# tinyPipes_v2_6.net
KiCad netlist of a schematic drawn in EAGLE
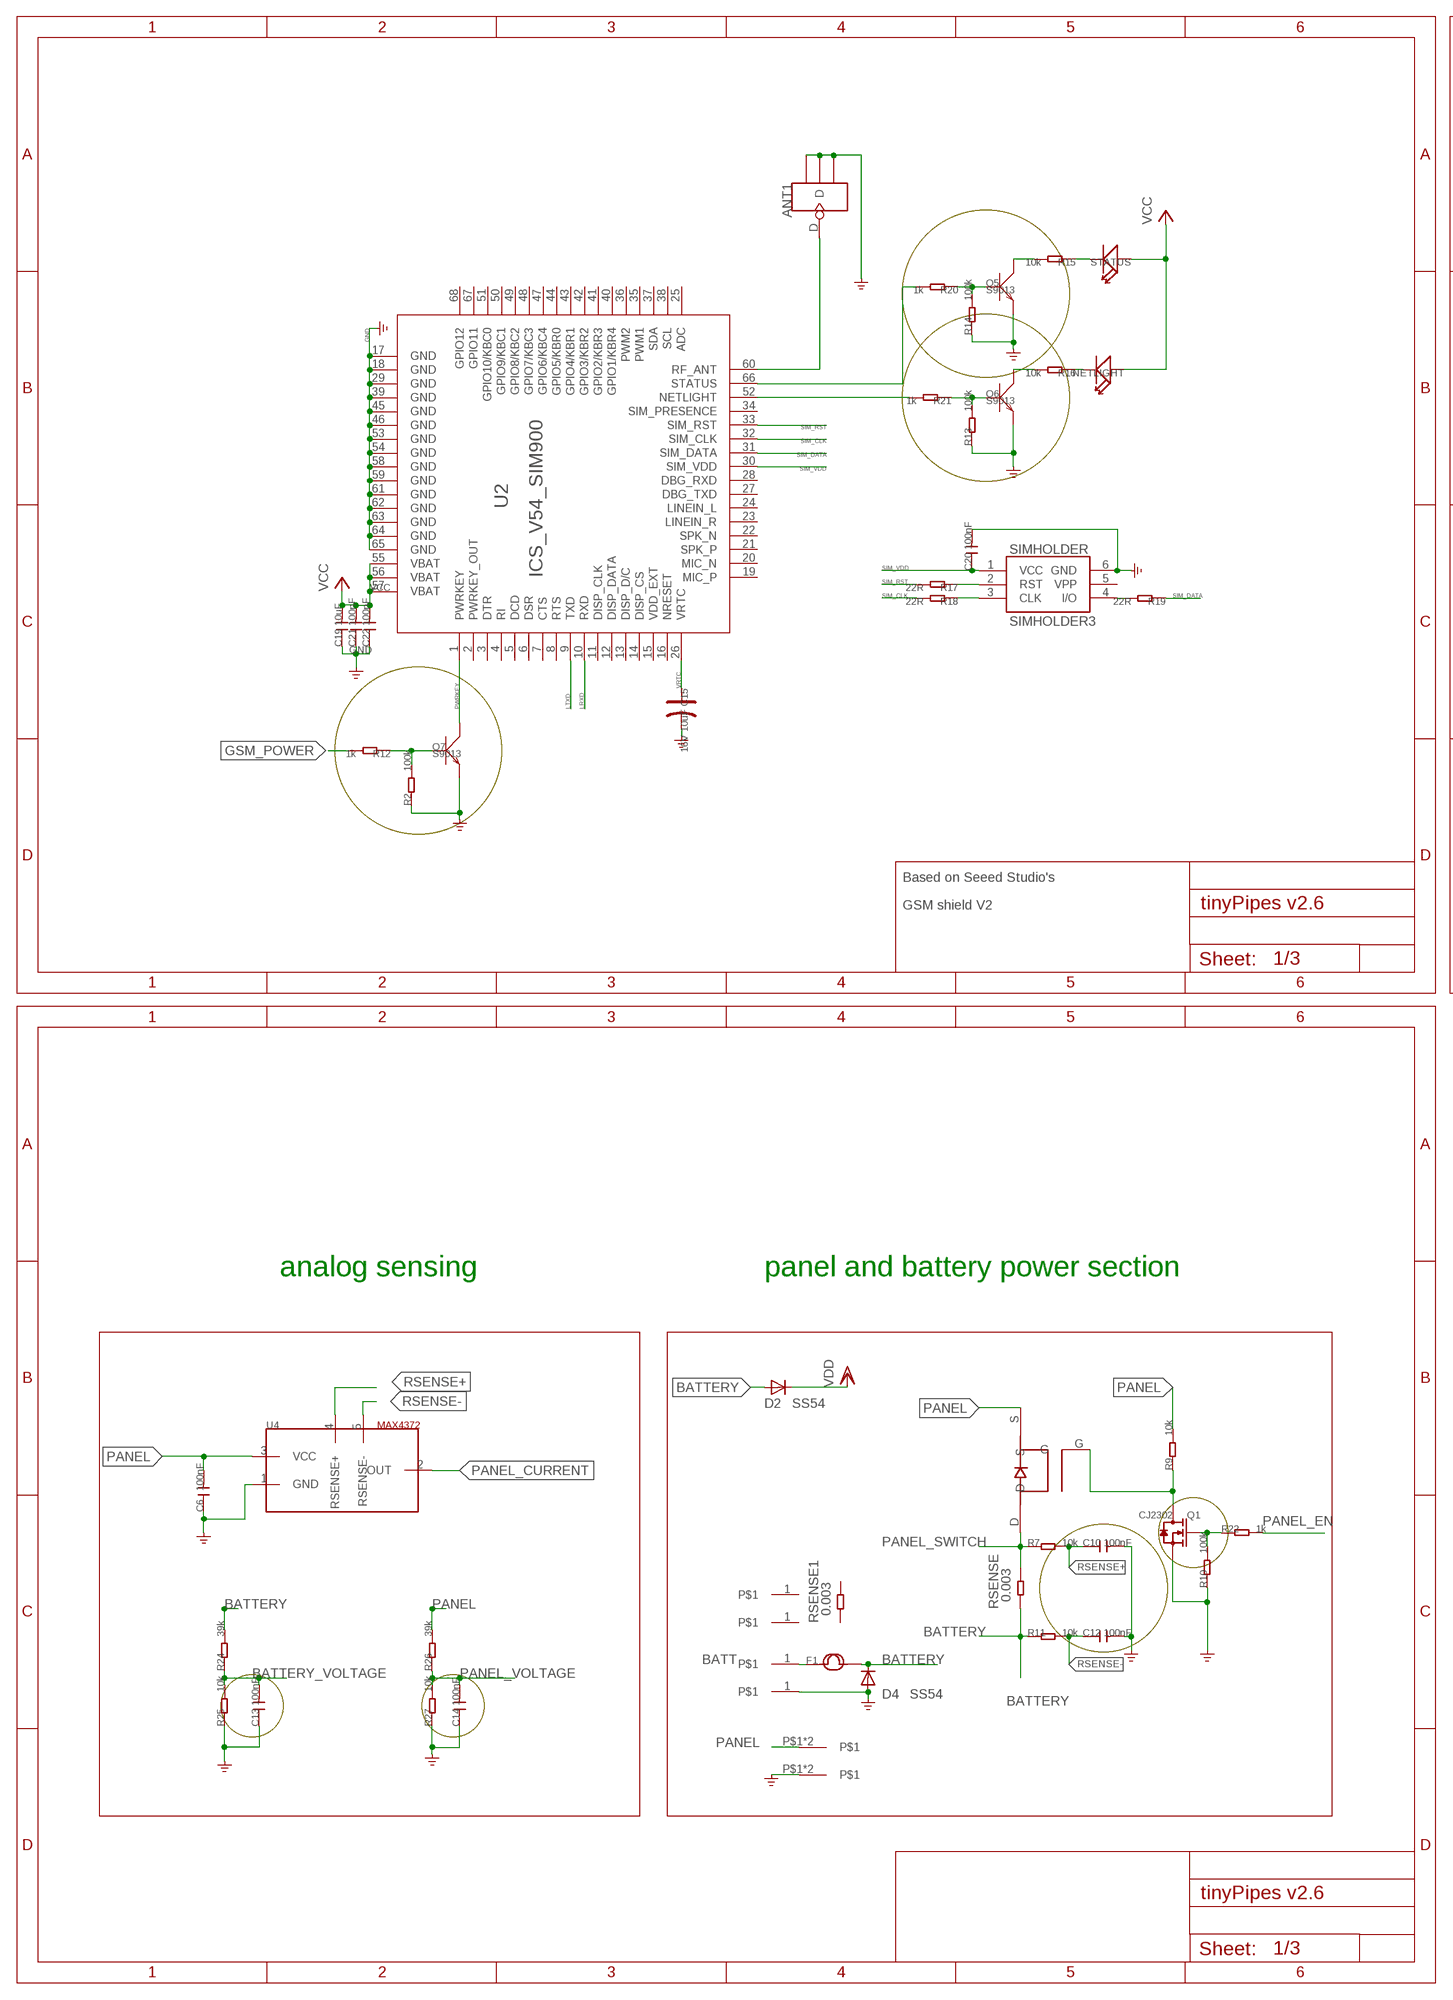
[diagram p0: schematic, sheet 1, part 1 of 2]
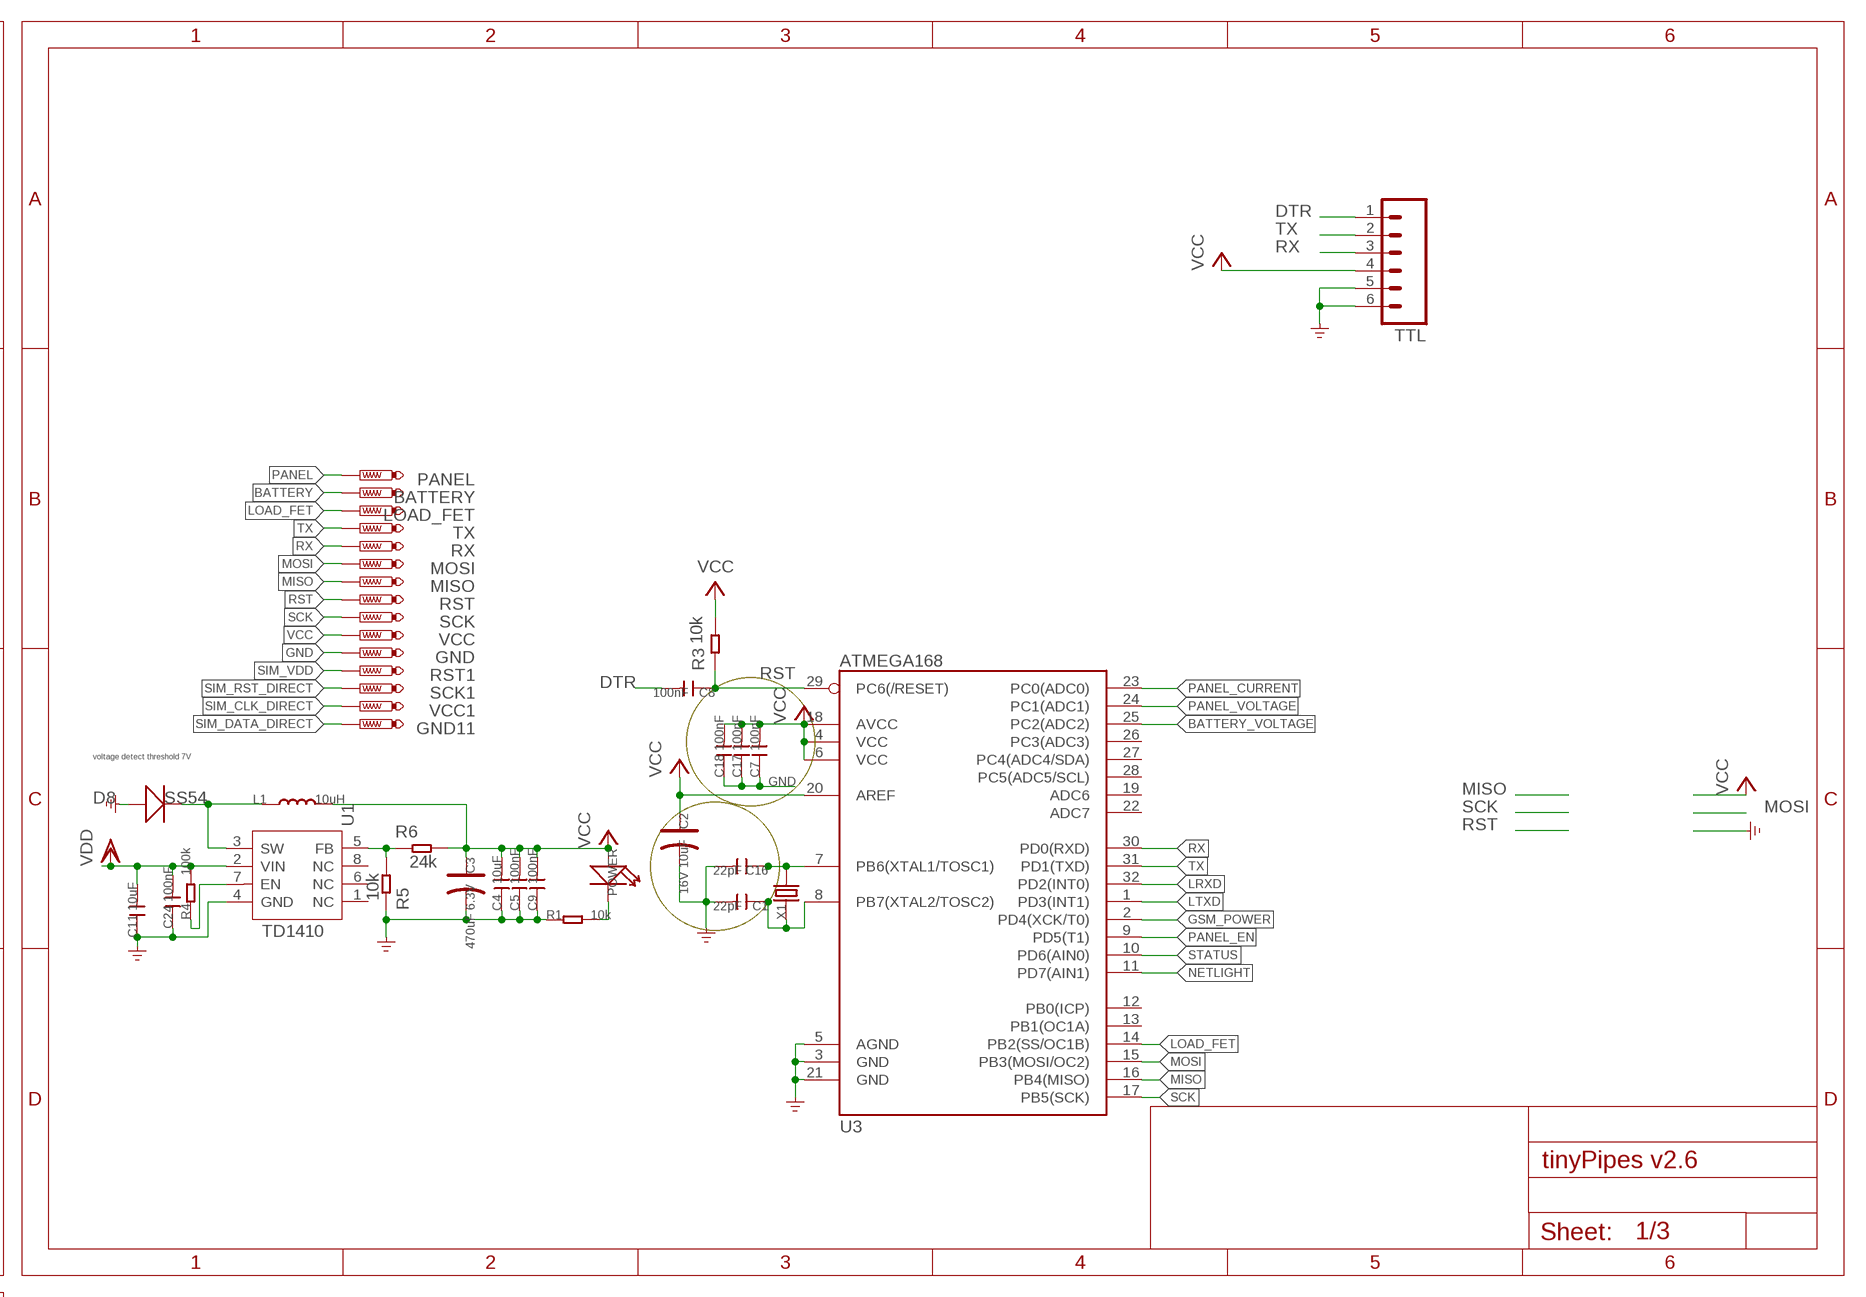
[diagram p1: schematic, sheet 1, part 2 of 2]

(export (version "E")
  (design (tool "Eeschema 10.0.6"))
  (components
    (comp (ref "ANT1")
      (value "ANTENNA-U-FL")
      (footprint "eagle-import:4P-U-FL")
      (libsource (lib "eagle-import") (part "ANTENNA-U-FL"))
    )
    (comp (ref "BATTERY")
      (value "PTR1B2,54")
      (footprint "eagle-import:B2,54")
      (libsource (lib "eagle-import") (part "PTR1B2,54"))
    )
    (comp (ref "BATTERY+")
      (value "TINYPIPES_BATTBATT")
      (footprint "eagle-import:TINYPIPES_BATT")
      (libsource (lib "eagle-import") (part "TINYPIPES_BATTBATT"))
    )
    (comp (ref "BATTERY+1")
      (value "TINYPIPES_BATTBATT")
      (footprint "eagle-import:TINYPIPES_BATT")
      (libsource (lib "eagle-import") (part "TINYPIPES_BATTBATT"))
    )
    (comp (ref "BATTERY-")
      (value "TINYPIPES_BATTBATT")
      (footprint "eagle-import:TINYPIPES_BATT")
      (libsource (lib "eagle-import") (part "TINYPIPES_BATTBATT"))
    )
    (comp (ref "BATTERY-1")
      (value "TINYPIPES_BATTBATT")
      (footprint "eagle-import:TINYPIPES_BATT")
      (libsource (lib "eagle-import") (part "TINYPIPES_BATTBATT"))
    )
    (comp (ref "C1")
      (value "22pF")
      (footprint "eagle-import:C0603")
      (libsource (lib "eagle-import") (part "C-0603"))
    )
    (comp (ref "C2")
      (value "16V 10uF")
      (footprint "eagle-import:AVX-A")
      (libsource (lib "eagle-import") (part "CAP-AVX-A"))
    )
    (comp (ref "C3")
      (value "470uF 6.3V")
      (footprint "eagle-import:AVX-D")
      (libsource (lib "eagle-import") (part "CAP-AVX-D"))
    )
    (comp (ref "C4")
      (value "10uF")
      (footprint "eagle-import:C0805")
      (libsource (lib "eagle-import") (part "C-0805"))
    )
    (comp (ref "C5")
      (value "100nF")
      (footprint "eagle-import:C0603")
      (libsource (lib "eagle-import") (part "C-0603"))
    )
    (comp (ref "C6")
      (value "100nF")
      (footprint "eagle-import:C0603")
      (libsource (lib "eagle-import") (part "C-0603"))
    )
    (comp (ref "C7")
      (value "100nF")
      (footprint "eagle-import:C0603")
      (libsource (lib "eagle-import") (part "C-0603"))
    )
    (comp (ref "C8")
      (value "100nF")
      (footprint "eagle-import:C0603")
      (libsource (lib "eagle-import") (part "C-0603"))
    )
    (comp (ref "C9")
      (value "100nF")
      (footprint "eagle-import:C0603")
      (libsource (lib "eagle-import") (part "C-0603"))
    )
    (comp (ref "C10")
      (value "100nF")
      (footprint "eagle-import:C0805")
      (libsource (lib "eagle-import") (part "C-0805"))
    )
    (comp (ref "C11")
      (value "10uF")
      (footprint "eagle-import:C0805")
      (libsource (lib "eagle-import") (part "C-0805"))
    )
    (comp (ref "C12")
      (value "100nF")
      (footprint "eagle-import:C0805")
      (libsource (lib "eagle-import") (part "C-0805"))
    )
    (comp (ref "C13")
      (value "100nF")
      (footprint "eagle-import:C0603")
      (libsource (lib "eagle-import") (part "C-0603"))
    )
    (comp (ref "C14")
      (value "100nF")
      (footprint "eagle-import:C0603")
      (libsource (lib "eagle-import") (part "C-0603"))
    )
    (comp (ref "C15")
      (value "16V 10uF")
      (footprint "eagle-import:AVX-A")
      (libsource (lib "eagle-import") (part "CAP-AVX-A"))
    )
    (comp (ref "C16")
      (value "22pF")
      (footprint "eagle-import:C0603")
      (libsource (lib "eagle-import") (part "C-0603"))
    )
    (comp (ref "C17")
      (value "100nF")
      (footprint "eagle-import:C0603")
      (libsource (lib "eagle-import") (part "C-0603"))
    )
    (comp (ref "C18")
      (value "100nF")
      (footprint "eagle-import:C0603")
      (libsource (lib "eagle-import") (part "C-0603"))
    )
    (comp (ref "C19")
      (value "10uF")
      (footprint "eagle-import:C0805")
      (libsource (lib "eagle-import") (part "C-0805"))
    )
    (comp (ref "C20")
      (value "100nF")
      (footprint "eagle-import:C0603")
      (libsource (lib "eagle-import") (part "C-0603"))
    )
    (comp (ref "C21")
      (value "100nF")
      (footprint "eagle-import:C0603")
      (libsource (lib "eagle-import") (part "C-0603"))
    )
    (comp (ref "C22")
      (value "100nF")
      (footprint "eagle-import:C0603")
      (libsource (lib "eagle-import") (part "C-0603"))
    )
    (comp (ref "C24")
      (value "100nF")
      (footprint "eagle-import:C0603")
      (libsource (lib "eagle-import") (part "C-0603"))
    )
    (comp (ref "D2")
      (value "SS54")
      (footprint "eagle-import:SMB")
      (libsource (lib "eagle-import") (part "DIODE-SMB"))
    )
    (comp (ref "D4")
      (value "SS54")
      (footprint "eagle-import:SMB")
      (libsource (lib "eagle-import") (part "DIODE-SMB"))
    )
    (comp (ref "D8")
      (value "SS54")
      (footprint "eagle-import:SMB")
      (libsource (lib "eagle-import") (part "D'MBRS240LT3'"))
    )
    (comp (ref "F1")
      (value "FUSE'16R700'")
      (footprint "eagle-import:0210")
      (libsource (lib "eagle-import") (part "FUSE'16R700'"))
    )
    (comp (ref "GND")
      (value "PTR1B2,54")
      (footprint "eagle-import:B2,54")
      (libsource (lib "eagle-import") (part "PTR1B2,54"))
    )
    (comp (ref "GND11")
      (value "PTR1B2,54")
      (footprint "eagle-import:B2,54")
      (libsource (lib "eagle-import") (part "PTR1B2,54"))
    )
    (comp (ref "L1")
      (value "10uH")
      (footprint "eagle-import:L0630")
      (libsource (lib "eagle-import") (part "L'0630'"))
    )
    (comp (ref "LOAD_FET")
      (value "PTR1B2,54")
      (footprint "eagle-import:B2,54")
      (libsource (lib "eagle-import") (part "PTR1B2,54"))
    )
    (comp (ref "MISO")
      (value "PTR1B2,54")
      (footprint "eagle-import:B2,54")
      (libsource (lib "eagle-import") (part "PTR1B2,54"))
    )
    (comp (ref "MOSI")
      (value "PTR1B2,54")
      (footprint "eagle-import:B2,54")
      (libsource (lib "eagle-import") (part "PTR1B2,54"))
    )
    (comp (ref "NETLIGHT")
      (value "LED'0603'")
      (footprint "eagle-import:LED-0603")
      (libsource (lib "eagle-import") (part "LED'0603'"))
    )
    (comp (ref "PANEL")
      (value "PTR1B2,54")
      (footprint "eagle-import:B2,54")
      (libsource (lib "eagle-import") (part "PTR1B2,54"))
    )
    (comp (ref "PANEL+")
      (value "TINYPIPES_BATTPANEL")
      (footprint "eagle-import:TINYPIPES_PANEL")
      (libsource (lib "eagle-import") (part "TINYPIPES_BATTPANEL"))
    )
    (comp (ref "PANEL-")
      (value "TINYPIPES_BATTPANEL")
      (footprint "eagle-import:TINYPIPES_PANEL")
      (libsource (lib "eagle-import") (part "TINYPIPES_BATTPANEL"))
    )
    (comp (ref "POWER")
      (value "LED'0603'")
      (footprint "eagle-import:LED-0603")
      (libsource (lib "eagle-import") (part "LED'0603'"))
    )
    (comp (ref "Q1")
      (value "CJ2302")
      (footprint "eagle-import:SOT23")
      (libsource (lib "eagle-import") (part "MOSFET-N'SOT23'"))
    )
    (comp (ref "Q5")
      (value "S9013")
      (footprint "eagle-import:SOT23")
      (libsource (lib "eagle-import") (part "TRANSISTOR-NPN-SOT23"))
    )
    (comp (ref "Q6")
      (value "S9013")
      (footprint "eagle-import:SOT23")
      (libsource (lib "eagle-import") (part "TRANSISTOR-NPN-SOT23"))
    )
    (comp (ref "Q7")
      (value "S9013")
      (footprint "eagle-import:SOT23")
      (libsource (lib "eagle-import") (part "TRANSISTOR-NPN-SOT23"))
    )
    (comp (ref "R1")
      (value "10k")
      (footprint "eagle-import:R0603")
      (libsource (lib "eagle-import") (part "R-0603"))
    )
    (comp (ref "R2")
      (value "100k")
      (footprint "eagle-import:R0603")
      (libsource (lib "eagle-import") (part "R-0603"))
    )
    (comp (ref "R3")
      (value "10k")
      (footprint "eagle-import:R0603")
      (libsource (lib "eagle-import") (part "R-0603"))
    )
    (comp (ref "R4")
      (value "100k")
      (footprint "eagle-import:R0603")
      (libsource (lib "eagle-import") (part "R-0603"))
    )
    (comp (ref "R5")
      (value "10k")
      (footprint "eagle-import:R0603")
      (libsource (lib "eagle-import") (part "R-0603"))
    )
    (comp (ref "R6")
      (value "24k")
      (footprint "eagle-import:R0603")
      (libsource (lib "eagle-import") (part "R-0603"))
    )
    (comp (ref "R7")
      (value "10k")
      (footprint "eagle-import:R0603")
      (libsource (lib "eagle-import") (part "R-0603"))
    )
    (comp (ref "R9")
      (value "10k")
      (footprint "eagle-import:R0603")
      (libsource (lib "eagle-import") (part "R-0603"))
    )
    (comp (ref "R10")
      (value "100k")
      (footprint "eagle-import:R0603")
      (libsource (lib "eagle-import") (part "R-0603"))
    )
    (comp (ref "R11")
      (value "10k")
      (footprint "eagle-import:R0603")
      (libsource (lib "eagle-import") (part "R-0603"))
    )
    (comp (ref "R12")
      (value "1k")
      (footprint "eagle-import:R0603")
      (libsource (lib "eagle-import") (part "R-0603"))
    )
    (comp (ref "R13")
      (value "100k")
      (footprint "eagle-import:R0603")
      (libsource (lib "eagle-import") (part "R-0603"))
    )
    (comp (ref "R14")
      (value "100k")
      (footprint "eagle-import:R0603")
      (libsource (lib "eagle-import") (part "R-0603"))
    )
    (comp (ref "R15")
      (value "10k")
      (footprint "eagle-import:R0603")
      (libsource (lib "eagle-import") (part "R-0603"))
    )
    (comp (ref "R16")
      (value "10k")
      (footprint "eagle-import:R0603")
      (libsource (lib "eagle-import") (part "R-0603"))
    )
    (comp (ref "R17")
      (value "22R")
      (footprint "eagle-import:R0603")
      (libsource (lib "eagle-import") (part "R-0603"))
    )
    (comp (ref "R18")
      (value "22R")
      (footprint "eagle-import:R0603")
      (libsource (lib "eagle-import") (part "R-0603"))
    )
    (comp (ref "R19")
      (value "22R")
      (footprint "eagle-import:R0603")
      (libsource (lib "eagle-import") (part "R-0603"))
    )
    (comp (ref "R20")
      (value "1k")
      (footprint "eagle-import:R0603")
      (libsource (lib "eagle-import") (part "R-0603"))
    )
    (comp (ref "R21")
      (value "1k")
      (footprint "eagle-import:R0603")
      (libsource (lib "eagle-import") (part "R-0603"))
    )
    (comp (ref "R22")
      (value "1k")
      (footprint "eagle-import:R0603")
      (libsource (lib "eagle-import") (part "R-0603"))
    )
    (comp (ref "R24")
      (value "39k")
      (footprint "eagle-import:R0603")
      (libsource (lib "eagle-import") (part "R-0603"))
    )
    (comp (ref "R25")
      (value "10k")
      (footprint "eagle-import:R0603")
      (libsource (lib "eagle-import") (part "R-0603"))
    )
    (comp (ref "R26")
      (value "39k")
      (footprint "eagle-import:R0603")
      (libsource (lib "eagle-import") (part "R-0603"))
    )
    (comp (ref "R27")
      (value "10k")
      (footprint "eagle-import:R0603")
      (libsource (lib "eagle-import") (part "R-0603"))
    )
    (comp (ref "RSENSE")
      (value "0.003")
      (footprint "eagle-import:R2512")
      (libsource (lib "eagle-import") (part "R-2512"))
    )
    (comp (ref "RSENSE1")
      (value "0.003")
      (footprint "eagle-import:R2512")
      (libsource (lib "eagle-import") (part "R-2512"))
    )
    (comp (ref "RST")
      (value "PTR1B2,54")
      (footprint "eagle-import:B2,54")
      (libsource (lib "eagle-import") (part "PTR1B2,54"))
    )
    (comp (ref "RST1")
      (value "PTR1B2,54")
      (footprint "eagle-import:B2,54")
      (libsource (lib "eagle-import") (part "PTR1B2,54"))
    )
    (comp (ref "RX")
      (value "PTR1B2,54")
      (footprint "eagle-import:B2,54")
      (libsource (lib "eagle-import") (part "PTR1B2,54"))
    )
    (comp (ref "SCK")
      (value "PTR1B2,54")
      (footprint "eagle-import:B2,54")
      (libsource (lib "eagle-import") (part "PTR1B2,54"))
    )
    (comp (ref "SCK1")
      (value "PTR1B2,54")
      (footprint "eagle-import:B2,54")
      (libsource (lib "eagle-import") (part "PTR1B2,54"))
    )
    (comp (ref "SIMHOLDER")
      (value "SIMHOLDER3")
      (footprint "eagle-import:SIMHOLDER3")
      (libsource (lib "eagle-import") (part "SIMHOLDER3"))
    )
    (comp (ref "STATUS")
      (value "LED'0603'")
      (footprint "eagle-import:LED-0603")
      (libsource (lib "eagle-import") (part "LED'0603'"))
    )
    (comp (ref "TTL")
      (value "M06LOCK")
      (footprint "eagle-import:1X06_LOCK")
      (libsource (lib "eagle-import") (part "M06LOCK"))
    )
    (comp (ref "TX")
      (value "PTR1B2,54")
      (footprint "eagle-import:B2,54")
      (libsource (lib "eagle-import") (part "PTR1B2,54"))
    )
    (comp (ref "U1")
      (value "TD1410")
      (footprint "eagle-import:SOP8")
      (libsource (lib "eagle-import") (part "TD1410"))
    )
    (comp (ref "U2")
      (value "ICS_V54_SIM900")
      (footprint "eagle-import:ICS_V54_SIM900")
      (libsource (lib "eagle-import") (part "ICS_V54_SIM900"))
    )
    (comp (ref "U3")
      (value "ATMEGA168")
      (footprint "eagle-import:TQFP32-08")
      (libsource (lib "eagle-import") (part "ATMEGA168"))
    )
    (comp (ref "U4")
      (value "MAX4372")
      (footprint "eagle-import:SOT23-5")
      (libsource (lib "eagle-import") (part "MAX4372"))
    )
    (comp (ref "U5")
      (value "SI4435POWER")
      (footprint "eagle-import:SO8_FET")
      (libsource (lib "eagle-import") (part "SI4435POWER"))
    )
    (comp (ref "VCC")
      (value "PTR1B2,54")
      (footprint "eagle-import:B2,54")
      (libsource (lib "eagle-import") (part "PTR1B2,54"))
    )
    (comp (ref "VCC1")
      (value "PTR1B2,54")
      (footprint "eagle-import:B2,54")
      (libsource (lib "eagle-import") (part "PTR1B2,54"))
    )
    (comp (ref "X1")
      (value "CRYSTAL'5032'")
      (footprint "eagle-import:2P-SMD-5X3.2")
      (libsource (lib "eagle-import") (part "CRYSTAL'5032'"))
    )
  )
  (nets
    (net (code "1") (name "BATT") (class "Default")
      (node (ref "BATTERY+") (pin "1") (pinfunction "P$1_1") (pintype "bidirectional"))
      (node (ref "F1") (pin "1") (pinfunction "1_1") (pintype "bidirectional"))
    )
    (net (code "2") (name "BATTERY") (class "Default")
      (node (ref "BATTERY") (pin "TP") (pinfunction "TP_TP") (pintype "input"))
      (node (ref "D2") (pin "A") (pinfunction "A_A") (pintype "passive"))
      (node (ref "D4") (pin "C") (pinfunction "C_C") (pintype "passive"))
      (node (ref "F1") (pin "2") (pinfunction "2_2") (pintype "bidirectional"))
      (node (ref "R11") (pin "1") (pinfunction "1_1") (pintype "passive"))
      (node (ref "R24") (pin "2") (pinfunction "2_2") (pintype "passive"))
      (node (ref "RSENSE") (pin "1") (pinfunction "1_1") (pintype "passive"))
    )
    (net (code "3") (name "BATTERY_VOLTAGE") (class "Default")
      (node (ref "C13") (pin "2") (pinfunction "2_2") (pintype "passive"))
      (node (ref "R24") (pin "1") (pinfunction "1_1") (pintype "passive"))
      (node (ref "R25") (pin "2") (pinfunction "2_2") (pintype "passive"))
      (node (ref "U3") (pin "25") (pinfunction "PC2(ADC2)_25") (pintype "bidirectional"))
    )
    (net (code "4") (name "DTR") (class "Default")
      (node (ref "C8") (pin "2") (pinfunction "2_2") (pintype "passive"))
      (node (ref "TTL") (pin "1") (pinfunction "1_1") (pintype "passive"))
    )
    (net (code "5") (name "GND") (class "Default")
      (node (ref "ANT1") (pin "GND1") (pinfunction "GND1_GND1") (pintype "bidirectional"))
      (node (ref "ANT1") (pin "GND2") (pinfunction "GND2_GND2") (pintype "bidirectional"))
      (node (ref "ANT1") (pin "GND3") (pinfunction "GND3_GND3") (pintype "bidirectional"))
      (node (ref "BATTERY-") (pin "1") (pinfunction "P$1_1") (pintype "bidirectional"))
      (node (ref "C1") (pin "2") (pinfunction "2_2") (pintype "passive"))
      (node (ref "C10") (pin "2") (pinfunction "2_2") (pintype "passive"))
      (node (ref "C11") (pin "1") (pinfunction "1_1") (pintype "passive"))
      (node (ref "C12") (pin "2") (pinfunction "2_2") (pintype "passive"))
      (node (ref "C13") (pin "1") (pinfunction "1_1") (pintype "passive"))
      (node (ref "C14") (pin "1") (pinfunction "1_1") (pintype "passive"))
      (node (ref "C15") (pin "-") (pinfunction "-_-") (pintype "passive"))
      (node (ref "C16") (pin "2") (pinfunction "2_2") (pintype "passive"))
      (node (ref "C17") (pin "1") (pinfunction "1_1") (pintype "passive"))
      (node (ref "C18") (pin "1") (pinfunction "1_1") (pintype "passive"))
      (node (ref "C19") (pin "1") (pinfunction "1_1") (pintype "passive"))
      (node (ref "C2") (pin "-") (pinfunction "-_-") (pintype "passive"))
      (node (ref "C20") (pin "2") (pinfunction "2_2") (pintype "passive"))
      (node (ref "C21") (pin "1") (pinfunction "1_1") (pintype "passive"))
      (node (ref "C22") (pin "1") (pinfunction "1_1") (pintype "passive"))
      (node (ref "C24") (pin "1") (pinfunction "1_1") (pintype "passive"))
      (node (ref "C3") (pin "-") (pinfunction "-_-") (pintype "passive"))
      (node (ref "C4") (pin "1") (pinfunction "1_1") (pintype "passive"))
      (node (ref "C5") (pin "1") (pinfunction "1_1") (pintype "passive"))
      (node (ref "C6") (pin "1") (pinfunction "1_1") (pintype "passive"))
      (node (ref "C7") (pin "1") (pinfunction "1_1") (pintype "passive"))
      (node (ref "C9") (pin "1") (pinfunction "1_1") (pintype "passive"))
      (node (ref "D4") (pin "A") (pinfunction "A_A") (pintype "passive"))
      (node (ref "D8") (pin "+") (pinfunction "+_+") (pintype "passive"))
      (node (ref "GND") (pin "TP") (pinfunction "TP_TP") (pintype "input"))
      (node (ref "PANEL-") (pin "P$1") (pinfunction "P$1_P$1") (pintype "bidirectional"))
      (node (ref "PANEL-") (pin "P$2") (pinfunction "P$1_P$2") (pintype "bidirectional"))
      (node (ref "Q1") (pin "2") (pinfunction "S_2") (pintype "passive"))
      (node (ref "Q5") (pin "2") (pinfunction "E_2") (pintype "passive"))
      (node (ref "Q6") (pin "2") (pinfunction "E_2") (pintype "passive"))
      (node (ref "Q7") (pin "2") (pinfunction "E_2") (pintype "passive"))
      (node (ref "R1") (pin "1") (pinfunction "1_1") (pintype "passive"))
      (node (ref "R10") (pin "1") (pinfunction "1_1") (pintype "passive"))
      (node (ref "R13") (pin "1") (pinfunction "1_1") (pintype "passive"))
      (node (ref "R14") (pin "1") (pinfunction "1_1") (pintype "passive"))
      (node (ref "R2") (pin "1") (pinfunction "1_1") (pintype "passive"))
      (node (ref "R25") (pin "1") (pinfunction "1_1") (pintype "passive"))
      (node (ref "R27") (pin "1") (pinfunction "1_1") (pintype "passive"))
      (node (ref "R5") (pin "2") (pinfunction "2_2") (pintype "passive"))
      (node (ref "SIMHOLDER") (pin "6") (pinfunction "GND_6") (pintype "bidirectional"))
      (node (ref "TTL") (pin "5") (pinfunction "5_5") (pintype "passive"))
      (node (ref "TTL") (pin "6") (pinfunction "6_6") (pintype "passive"))
      (node (ref "U1") (pin "4") (pinfunction "GND_4") (pintype "power_in"))
      (node (ref "U2") (pin "17") (pinfunction "GND_17") (pintype "power_in"))
      (node (ref "U2") (pin "18") (pinfunction "GND_18") (pintype "power_in"))
      (node (ref "U2") (pin "29") (pinfunction "GND_29") (pintype "power_in"))
      (node (ref "U2") (pin "39") (pinfunction "GND_39") (pintype "power_in"))
      (node (ref "U2") (pin "45") (pinfunction "GND_45") (pintype "power_in"))
      (node (ref "U2") (pin "46") (pinfunction "GND_46") (pintype "power_in"))
      (node (ref "U2") (pin "53") (pinfunction "GND_53") (pintype "power_in"))
      (node (ref "U2") (pin "54") (pinfunction "GND_54") (pintype "power_in"))
      (node (ref "U2") (pin "58") (pinfunction "GND_58") (pintype "power_in"))
      (node (ref "U2") (pin "59") (pinfunction "GND_59") (pintype "power_in"))
      (node (ref "U2") (pin "61") (pinfunction "GND_61") (pintype "power_in"))
      (node (ref "U2") (pin "62") (pinfunction "GND_62") (pintype "power_in"))
      (node (ref "U2") (pin "63") (pinfunction "GND_63") (pintype "power_in"))
      (node (ref "U2") (pin "64") (pinfunction "GND_64") (pintype "power_in"))
      (node (ref "U2") (pin "65") (pinfunction "GND_65") (pintype "power_in"))
      (node (ref "U3") (pin "21") (pinfunction "GND_21") (pintype "bidirectional"))
      (node (ref "U3") (pin "3") (pinfunction "GND_3") (pintype "bidirectional"))
      (node (ref "U3") (pin "5") (pinfunction "AGND_5") (pintype "bidirectional"))
      (node (ref "U4") (pin "1") (pinfunction "GND_1") (pintype "bidirectional"))
    )
    (net (code "6") (name "GSM_POWER") (class "Default")
      (node (ref "R12") (pin "2") (pinfunction "2_2") (pintype "passive"))
      (node (ref "U3") (pin "2") (pinfunction "PD4(XCK/T0)_2") (pintype "bidirectional"))
    )
    (net (code "7") (name "LOAD_FET") (class "Default")
      (node (ref "LOAD_FET") (pin "TP") (pinfunction "TP_TP") (pintype "input"))
      (node (ref "U3") (pin "14") (pinfunction "PB2(SS/OC1B)_14") (pintype "bidirectional"))
    )
    (net (code "8") (name "LRXD") (class "Default")
      (node (ref "U2") (pin "10") (pinfunction "RXD_10") (pintype "input"))
      (node (ref "U3") (pin "32") (pinfunction "PD2(INT0)_32") (pintype "bidirectional"))
    )
    (net (code "9") (name "LTXD") (class "Default")
      (node (ref "U2") (pin "9") (pinfunction "TXD_9") (pintype "output"))
      (node (ref "U3") (pin "1") (pinfunction "PD3(INT1)_1") (pintype "bidirectional"))
    )
    (net (code "10") (name "MISO") (class "Default")
      (node (ref "MISO") (pin "TP") (pinfunction "TP_TP") (pintype "input"))
      (node (ref "U3") (pin "16") (pinfunction "PB4(MISO)_16") (pintype "bidirectional"))
    )
    (net (code "11") (name "MOSI") (class "Default")
      (node (ref "MOSI") (pin "TP") (pinfunction "TP_TP") (pintype "input"))
      (node (ref "U3") (pin "15") (pinfunction "PB3(MOSI/OC2)_15") (pintype "bidirectional"))
    )
    (net (code "12") (name "NETLIGHT") (class "Default")
      (node (ref "R21") (pin "2") (pinfunction "2_2") (pintype "passive"))
      (node (ref "U2") (pin "52") (pinfunction "NETLIGHT_52") (pintype "output"))
      (node (ref "U3") (pin "11") (pinfunction "PD7(AIN1)_11") (pintype "bidirectional"))
    )
    (net (code "13") (name "Net-(NETLIGHT-Pad-)") (class "Default")
      (node (ref "NETLIGHT") (pin "-") (pinfunction "-_-") (pintype "passive"))
      (node (ref "R16") (pin "1") (pinfunction "1_1") (pintype "passive"))
    )
    (net (code "14") (name "Net-(POWER-Pad-)") (class "Default")
      (node (ref "POWER") (pin "-") (pinfunction "-_-") (pintype "passive"))
      (node (ref "R1") (pin "2") (pinfunction "2_2") (pintype "passive"))
    )
    (net (code "15") (name "Net-(Q1-D)") (class "Default")
      (node (ref "Q1") (pin "3") (pinfunction "D_3") (pintype "passive"))
      (node (ref "R9") (pin "1") (pinfunction "1_1") (pintype "passive"))
      (node (ref "U5") (pin "G") (pinfunction "G_G") (pintype "bidirectional"))
    )
    (net (code "16") (name "Net-(Q1-G)") (class "Default")
      (node (ref "Q1") (pin "1") (pinfunction "G_1") (pintype "passive"))
      (node (ref "R10") (pin "2") (pinfunction "2_2") (pintype "passive"))
      (node (ref "R22") (pin "1") (pinfunction "1_1") (pintype "passive"))
    )
    (net (code "17") (name "Net-(Q5-B)") (class "Default")
      (node (ref "Q5") (pin "1") (pinfunction "B_1") (pintype "passive"))
      (node (ref "R14") (pin "2") (pinfunction "2_2") (pintype "passive"))
      (node (ref "R20") (pin "1") (pinfunction "1_1") (pintype "passive"))
    )
    (net (code "18") (name "Net-(Q5-C)") (class "Default")
      (node (ref "Q5") (pin "3") (pinfunction "C_3") (pintype "passive"))
      (node (ref "R15") (pin "2") (pinfunction "2_2") (pintype "passive"))
    )
    (net (code "19") (name "Net-(Q6-B)") (class "Default")
      (node (ref "Q6") (pin "1") (pinfunction "B_1") (pintype "passive"))
      (node (ref "R13") (pin "2") (pinfunction "2_2") (pintype "passive"))
      (node (ref "R21") (pin "1") (pinfunction "1_1") (pintype "passive"))
    )
    (net (code "20") (name "Net-(Q6-C)") (class "Default")
      (node (ref "Q6") (pin "3") (pinfunction "C_3") (pintype "passive"))
      (node (ref "R16") (pin "2") (pinfunction "2_2") (pintype "passive"))
    )
    (net (code "21") (name "Net-(Q7-B)") (class "Default")
      (node (ref "Q7") (pin "1") (pinfunction "B_1") (pintype "passive"))
      (node (ref "R12") (pin "1") (pinfunction "1_1") (pintype "passive"))
      (node (ref "R2") (pin "2") (pinfunction "2_2") (pintype "passive"))
    )
    (net (code "22") (name "Net-(R15-Pad1)") (class "Default")
      (node (ref "R15") (pin "1") (pinfunction "1_1") (pintype "passive"))
      (node (ref "STATUS") (pin "-") (pinfunction "-_-") (pintype "passive"))
    )
    (net (code "23") (name "Net-(U1-EN)") (class "Default")
      (node (ref "R4") (pin "1") (pinfunction "1_1") (pintype "passive"))
      (node (ref "U1") (pin "7") (pinfunction "EN_7") (pintype "input"))
    )
    (net (code "24") (name "Net-(U1-FB)") (class "Default")
      (node (ref "R5") (pin "1") (pinfunction "1_1") (pintype "passive"))
      (node (ref "R6") (pin "1") (pinfunction "1_1") (pintype "passive"))
      (node (ref "U1") (pin "5") (pinfunction "FB_5") (pintype "input"))
    )
    (net (code "25") (name "Net-(U1-SW)") (class "Default")
      (node (ref "D8") (pin "-") (pinfunction "-_-") (pintype "passive"))
      (node (ref "L1") (pin "1") (pinfunction "1_1") (pintype "passive"))
      (node (ref "U1") (pin "3") (pinfunction "SW_3") (pintype "output"))
    )
    (net (code "26") (name "Net-(U2-RF_ANT)") (class "Default")
      (node (ref "ANT1") (pin "D") (pinfunction "D_D") (pintype "bidirectional"))
      (node (ref "U2") (pin "60") (pinfunction "RF_ANT_60") (pintype "bidirectional"))
    )
    (net (code "27") (name "Net-(U3-PB6(XTAL1{slash}TOSC1))") (class "Default")
      (node (ref "C16") (pin "1") (pinfunction "1_1") (pintype "passive"))
      (node (ref "U3") (pin "7") (pinfunction "PB6(XTAL1/TOSC1)_7") (pintype "bidirectional"))
      (node (ref "X1") (pin "2") (pinfunction "2_2") (pintype "passive"))
    )
    (net (code "28") (name "Net-(U3-PB7(XTAL2{slash}TOSC2))") (class "Default")
      (node (ref "C1") (pin "1") (pinfunction "1_1") (pintype "passive"))
      (node (ref "U3") (pin "8") (pinfunction "PB7(XTAL2/TOSC2)_8") (pintype "bidirectional"))
      (node (ref "X1") (pin "1") (pinfunction "1_1") (pintype "passive"))
    )
    (net (code "29") (name "PANEL") (class "Default")
      (node (ref "C6") (pin "2") (pinfunction "2_2") (pintype "passive"))
      (node (ref "PANEL") (pin "TP") (pinfunction "TP_TP") (pintype "input"))
      (node (ref "PANEL+") (pin "P$1") (pinfunction "P$1_P$1") (pintype "bidirectional"))
      (node (ref "PANEL+") (pin "P$2") (pinfunction "P$1_P$2") (pintype "bidirectional"))
      (node (ref "R26") (pin "2") (pinfunction "2_2") (pintype "passive"))
      (node (ref "R9") (pin "2") (pinfunction "2_2") (pintype "passive"))
      (node (ref "U4") (pin "3") (pinfunction "VCC_3") (pintype "bidirectional"))
      (node (ref "U5") (pin "S") (pinfunction "S_S") (pintype "bidirectional"))
    )
    (net (code "30") (name "PANEL_CURRENT") (class "Default")
      (node (ref "U3") (pin "23") (pinfunction "PC0(ADC0)_23") (pintype "bidirectional"))
      (node (ref "U4") (pin "2") (pinfunction "OUT_2") (pintype "bidirectional"))
    )
    (net (code "31") (name "PANEL_EN") (class "Default")
      (node (ref "R22") (pin "2") (pinfunction "2_2") (pintype "passive"))
      (node (ref "U3") (pin "9") (pinfunction "PD5(T1)_9") (pintype "bidirectional"))
    )
    (net (code "32") (name "PANEL_SWITCH") (class "Default")
      (node (ref "R7") (pin "1") (pinfunction "1_1") (pintype "passive"))
      (node (ref "RSENSE") (pin "2") (pinfunction "2_2") (pintype "passive"))
      (node (ref "U5") (pin "D") (pinfunction "D_D") (pintype "bidirectional"))
    )
    (net (code "33") (name "PANEL_VOLTAGE") (class "Default")
      (node (ref "C14") (pin "2") (pinfunction "2_2") (pintype "passive"))
      (node (ref "R26") (pin "1") (pinfunction "1_1") (pintype "passive"))
      (node (ref "R27") (pin "2") (pinfunction "2_2") (pintype "passive"))
      (node (ref "U3") (pin "24") (pinfunction "PC1(ADC1)_24") (pintype "bidirectional"))
    )
    (net (code "34") (name "PWRKEY") (class "Default")
      (node (ref "Q7") (pin "3") (pinfunction "C_3") (pintype "passive"))
      (node (ref "U2") (pin "1") (pinfunction "PWRKEY_1") (pintype "input"))
    )
    (net (code "35") (name "RSENSE+") (class "Default")
      (node (ref "C10") (pin "1") (pinfunction "1_1") (pintype "passive"))
      (node (ref "R7") (pin "2") (pinfunction "2_2") (pintype "passive"))
      (node (ref "U4") (pin "4") (pinfunction "RSENSE+_4") (pintype "bidirectional"))
    )
    (net (code "36") (name "RSENSE-") (class "Default")
      (node (ref "C12") (pin "1") (pinfunction "1_1") (pintype "passive"))
      (node (ref "R11") (pin "2") (pinfunction "2_2") (pintype "passive"))
      (node (ref "U4") (pin "5") (pinfunction "RSENSE-_5") (pintype "bidirectional"))
    )
    (net (code "37") (name "RST") (class "Default")
      (node (ref "C8") (pin "1") (pinfunction "1_1") (pintype "passive"))
      (node (ref "R3") (pin "1") (pinfunction "1_1") (pintype "passive"))
      (node (ref "RST") (pin "TP") (pinfunction "TP_TP") (pintype "input"))
      (node (ref "U3") (pin "29") (pinfunction "PC6(/RESET)_29") (pintype "bidirectional"))
    )
    (net (code "38") (name "RX") (class "Default")
      (node (ref "RX") (pin "TP") (pinfunction "TP_TP") (pintype "input"))
      (node (ref "TTL") (pin "3") (pinfunction "3_3") (pintype "passive"))
      (node (ref "U3") (pin "30") (pinfunction "PD0(RXD)_30") (pintype "bidirectional"))
    )
    (net (code "39") (name "SCK") (class "Default")
      (node (ref "SCK") (pin "TP") (pinfunction "TP_TP") (pintype "input"))
      (node (ref "U3") (pin "17") (pinfunction "PB5(SCK)_17") (pintype "bidirectional"))
    )
    (net (code "40") (name "SIM_CLK") (class "Default")
      (node (ref "R18") (pin "2") (pinfunction "2_2") (pintype "passive"))
      (node (ref "U2") (pin "32") (pinfunction "SIM_CLK_32") (pintype "output"))
    )
    (net (code "41") (name "SIM_CLK_DIRECT") (class "Default")
      (node (ref "R18") (pin "1") (pinfunction "1_1") (pintype "passive"))
      (node (ref "SIMHOLDER") (pin "3") (pinfunction "CLK_3") (pintype "bidirectional"))
      (node (ref "VCC1") (pin "TP") (pinfunction "TP_TP") (pintype "input"))
    )
    (net (code "42") (name "SIM_DATA") (class "Default")
      (node (ref "R19") (pin "1") (pinfunction "1_1") (pintype "passive"))
      (node (ref "U2") (pin "31") (pinfunction "SIM_DATA_31") (pintype "bidirectional"))
    )
    (net (code "43") (name "SIM_DATA_DIRECT") (class "Default")
      (node (ref "GND11") (pin "TP") (pinfunction "TP_TP") (pintype "input"))
      (node (ref "R19") (pin "2") (pinfunction "2_2") (pintype "passive"))
      (node (ref "SIMHOLDER") (pin "4") (pinfunction "I/O_4") (pintype "bidirectional"))
    )
    (net (code "44") (name "SIM_RST") (class "Default")
      (node (ref "R17") (pin "2") (pinfunction "2_2") (pintype "passive"))
      (node (ref "U2") (pin "33") (pinfunction "SIM_RST_33") (pintype "output"))
    )
    (net (code "45") (name "SIM_RST_DIRECT") (class "Default")
      (node (ref "R17") (pin "1") (pinfunction "1_1") (pintype "passive"))
      (node (ref "SCK1") (pin "TP") (pinfunction "TP_TP") (pintype "input"))
      (node (ref "SIMHOLDER") (pin "2") (pinfunction "RST_2") (pintype "bidirectional"))
    )
    (net (code "46") (name "SIM_VDD") (class "Default")
      (node (ref "C20") (pin "1") (pinfunction "1_1") (pintype "passive"))
      (node (ref "RST1") (pin "TP") (pinfunction "TP_TP") (pintype "input"))
      (node (ref "SIMHOLDER") (pin "1") (pinfunction "VCC_1") (pintype "bidirectional"))
      (node (ref "U2") (pin "30") (pinfunction "SIM_VDD_30") (pintype "output"))
    )
    (net (code "47") (name "STATUS") (class "Default")
      (node (ref "R20") (pin "2") (pinfunction "2_2") (pintype "passive"))
      (node (ref "U2") (pin "66") (pinfunction "STATUS_66") (pintype "output"))
      (node (ref "U3") (pin "10") (pinfunction "PD6(AIN0)_10") (pintype "bidirectional"))
    )
    (net (code "48") (name "TX") (class "Default")
      (node (ref "TTL") (pin "2") (pinfunction "2_2") (pintype "passive"))
      (node (ref "TX") (pin "TP") (pinfunction "TP_TP") (pintype "input"))
      (node (ref "U3") (pin "31") (pinfunction "PD1(TXD)_31") (pintype "bidirectional"))
    )
    (net (code "49") (name "VCC") (class "Default")
      (node (ref "C17") (pin "2") (pinfunction "2_2") (pintype "passive"))
      (node (ref "C18") (pin "2") (pinfunction "2_2") (pintype "passive"))
      (node (ref "C19") (pin "2") (pinfunction "2_2") (pintype "passive"))
      (node (ref "C2") (pin "+") (pinfunction "+_+") (pintype "passive"))
      (node (ref "C21") (pin "2") (pinfunction "2_2") (pintype "passive"))
      (node (ref "C22") (pin "2") (pinfunction "2_2") (pintype "passive"))
      (node (ref "C3") (pin "+") (pinfunction "+_+") (pintype "passive"))
      (node (ref "C4") (pin "2") (pinfunction "2_2") (pintype "passive"))
      (node (ref "C5") (pin "2") (pinfunction "2_2") (pintype "passive"))
      (node (ref "C7") (pin "2") (pinfunction "2_2") (pintype "passive"))
      (node (ref "C9") (pin "2") (pinfunction "2_2") (pintype "passive"))
      (node (ref "L1") (pin "2") (pinfunction "2_2") (pintype "passive"))
      (node (ref "NETLIGHT") (pin "+") (pinfunction "+_+") (pintype "passive"))
      (node (ref "POWER") (pin "+") (pinfunction "+_+") (pintype "passive"))
      (node (ref "R3") (pin "2") (pinfunction "2_2") (pintype "passive"))
      (node (ref "R6") (pin "2") (pinfunction "2_2") (pintype "passive"))
      (node (ref "STATUS") (pin "+") (pinfunction "+_+") (pintype "passive"))
      (node (ref "TTL") (pin "4") (pinfunction "4_4") (pintype "passive"))
      (node (ref "U2") (pin "55") (pinfunction "VBAT_55") (pintype "power_in"))
      (node (ref "U2") (pin "56") (pinfunction "VBAT_56") (pintype "power_in"))
      (node (ref "U2") (pin "57") (pinfunction "VBAT_57") (pintype "power_in"))
      (node (ref "U3") (pin "18") (pinfunction "AVCC_18") (pintype "bidirectional"))
      (node (ref "U3") (pin "20") (pinfunction "AREF_20") (pintype "bidirectional"))
      (node (ref "U3") (pin "4") (pinfunction "VCC_4") (pintype "bidirectional"))
      (node (ref "U3") (pin "6") (pinfunction "VCC_6") (pintype "bidirectional"))
      (node (ref "VCC") (pin "TP") (pinfunction "TP_TP") (pintype "input"))
    )
    (net (code "50") (name "VDD") (class "Default")
      (node (ref "C11") (pin "2") (pinfunction "2_2") (pintype "passive"))
      (node (ref "C24") (pin "2") (pinfunction "2_2") (pintype "passive"))
      (node (ref "D2") (pin "C") (pinfunction "C_C") (pintype "passive"))
      (node (ref "R4") (pin "2") (pinfunction "2_2") (pintype "passive"))
      (node (ref "U1") (pin "2") (pinfunction "VIN_2") (pintype "input"))
    )
    (net (code "51") (name "VRTC") (class "Default")
      (node (ref "C15") (pin "+") (pinfunction "+_+") (pintype "passive"))
      (node (ref "U2") (pin "26") (pinfunction "VRTC_26") (pintype "bidirectional"))
    )
    (net (code "52") (name "unconnected-(BATTERY+1-P$1-Pad1)") (class "Default")
      (node (ref "BATTERY+1") (pin "1") (pinfunction "P$1_1") (pintype "bidirectional"))
    )
    (net (code "53") (name "unconnected-(BATTERY-1-P$1-Pad1)") (class "Default")
      (node (ref "BATTERY-1") (pin "1") (pinfunction "P$1_1") (pintype "bidirectional"))
    )
    (net (code "54") (name "unconnected-(RSENSE1-Pad1)") (class "Default")
      (node (ref "RSENSE1") (pin "1") (pinfunction "1_1") (pintype "passive"))
    )
    (net (code "55") (name "unconnected-(RSENSE1-Pad2)") (class "Default")
      (node (ref "RSENSE1") (pin "2") (pinfunction "2_2") (pintype "passive"))
    )
    (net (code "56") (name "unconnected-(SIMHOLDER-VPP-Pad5)") (class "Default")
      (node (ref "SIMHOLDER") (pin "5") (pinfunction "VPP_5") (pintype "bidirectional"))
    )
    (net (code "57") (name "unconnected-(U1-NC-Pad1)") (class "Default")
      (node (ref "U1") (pin "1") (pinfunction "NC_1") (pintype "no_connect"))
    )
    (net (code "58") (name "unconnected-(U1-NC-Pad6)") (class "Default")
      (node (ref "U1") (pin "6") (pinfunction "NC_6") (pintype "no_connect"))
    )
    (net (code "59") (name "unconnected-(U1-NC-Pad8)") (class "Default")
      (node (ref "U1") (pin "8") (pinfunction "NC_8") (pintype "no_connect"))
    )
    (net (code "60") (name "unconnected-(U2-ADC-Pad25)") (class "Default")
      (node (ref "U2") (pin "25") (pinfunction "ADC_25") (pintype "input"))
    )
    (net (code "61") (name "unconnected-(U2-CTS-Pad7)") (class "Default")
      (node (ref "U2") (pin "7") (pinfunction "CTS_7") (pintype "output"))
    )
    (net (code "62") (name "unconnected-(U2-DBG_RXD-Pad28)") (class "Default")
      (node (ref "U2") (pin "28") (pinfunction "DBG_RXD_28") (pintype "input"))
    )
    (net (code "63") (name "unconnected-(U2-DBG_TXD-Pad27)") (class "Default")
      (node (ref "U2") (pin "27") (pinfunction "DBG_TXD_27") (pintype "output"))
    )
    (net (code "64") (name "unconnected-(U2-DCD-Pad5)") (class "Default")
      (node (ref "U2") (pin "5") (pinfunction "DCD_5") (pintype "output"))
    )
    (net (code "65") (name "unconnected-(U2-DISP_CLK-Pad11)") (class "Default")
      (node (ref "U2") (pin "11") (pinfunction "DISP_CLK_11") (pintype "output"))
    )
    (net (code "66") (name "unconnected-(U2-DISP_CS-Pad14)") (class "Default")
      (node (ref "U2") (pin "14") (pinfunction "DISP_CS_14") (pintype "output"))
    )
    (net (code "67") (name "unconnected-(U2-DISP_DATA-Pad12)") (class "Default")
      (node (ref "U2") (pin "12") (pinfunction "DISP_DATA_12") (pintype "bidirectional"))
    )
    (net (code "68") (name "unconnected-(U2-DISP_D{slash}C-Pad13)") (class "Default")
      (node (ref "U2") (pin "13") (pinfunction "DISP_D/C_13") (pintype "output"))
    )
    (net (code "69") (name "unconnected-(U2-DSR-Pad6)") (class "Default")
      (node (ref "U2") (pin "6") (pinfunction "DSR_6") (pintype "output"))
    )
    (net (code "70") (name "unconnected-(U2-DTR-Pad3)") (class "Default")
      (node (ref "U2") (pin "3") (pinfunction "DTR_3") (pintype "input"))
    )
    (net (code "71") (name "unconnected-(U2-GPIO1{slash}KBR4-Pad40)") (class "Default")
      (node (ref "U2") (pin "40") (pinfunction "GPIO1/KBR4_40") (pintype "output"))
    )
    (net (code "72") (name "unconnected-(U2-GPIO2{slash}KBR3-Pad41)") (class "Default")
      (node (ref "U2") (pin "41") (pinfunction "GPIO2/KBR3_41") (pintype "output"))
    )
    (net (code "73") (name "unconnected-(U2-GPIO3{slash}KBR2-Pad42)") (class "Default")
      (node (ref "U2") (pin "42") (pinfunction "GPIO3/KBR2_42") (pintype "output"))
    )
    (net (code "74") (name "unconnected-(U2-GPIO4{slash}KBR1-Pad43)") (class "Default")
      (node (ref "U2") (pin "43") (pinfunction "GPIO4/KBR1_43") (pintype "output"))
    )
    (net (code "75") (name "unconnected-(U2-GPIO5{slash}KBR0-Pad44)") (class "Default")
      (node (ref "U2") (pin "44") (pinfunction "GPIO5/KBR0_44") (pintype "output"))
    )
    (net (code "76") (name "unconnected-(U2-GPIO6{slash}KBC4-Pad47)") (class "Default")
      (node (ref "U2") (pin "47") (pinfunction "GPIO6/KBC4_47") (pintype "input"))
    )
    (net (code "77") (name "unconnected-(U2-GPIO7{slash}KBC3-Pad48)") (class "Default")
      (node (ref "U2") (pin "48") (pinfunction "GPIO7/KBC3_48") (pintype "bidirectional"))
    )
    (net (code "78") (name "unconnected-(U2-GPIO8{slash}KBC2-Pad49)") (class "Default")
      (node (ref "U2") (pin "49") (pinfunction "GPIO8/KBC2_49") (pintype "input"))
    )
    (net (code "79") (name "unconnected-(U2-GPIO9{slash}KBC1-Pad50)") (class "Default")
      (node (ref "U2") (pin "50") (pinfunction "GPIO9/KBC1_50") (pintype "input"))
    )
    (net (code "80") (name "unconnected-(U2-GPIO10{slash}KBC0-Pad51)") (class "Default")
      (node (ref "U2") (pin "51") (pinfunction "GPIO10/KBC0_51") (pintype "bidirectional"))
    )
    (net (code "81") (name "unconnected-(U2-GPIO11-Pad67)") (class "Default")
      (node (ref "U2") (pin "67") (pinfunction "GPIO11_67") (pintype "bidirectional"))
    )
    (net (code "82") (name "unconnected-(U2-GPIO12-Pad68)") (class "Default")
      (node (ref "U2") (pin "68") (pinfunction "GPIO12_68") (pintype "bidirectional"))
    )
    (net (code "83") (name "unconnected-(U2-LINEIN_L-Pad24)") (class "Default")
      (node (ref "U2") (pin "24") (pinfunction "LINEIN_L_24") (pintype "input"))
    )
    (net (code "84") (name "unconnected-(U2-LINEIN_R-Pad23)") (class "Default")
      (node (ref "U2") (pin "23") (pinfunction "LINEIN_R_23") (pintype "input"))
    )
    (net (code "85") (name "unconnected-(U2-MIC_N-Pad20)") (class "Default")
      (node (ref "U2") (pin "20") (pinfunction "MIC_N_20") (pintype "input"))
    )
    (net (code "86") (name "unconnected-(U2-MIC_P-Pad19)") (class "Default")
      (node (ref "U2") (pin "19") (pinfunction "MIC_P_19") (pintype "input"))
    )
    (net (code "87") (name "unconnected-(U2-NRESET-Pad16)") (class "Default")
      (node (ref "U2") (pin "16") (pinfunction "NRESET_16") (pintype "input"))
    )
    (net (code "88") (name "unconnected-(U2-PWM1-Pad35)") (class "Default")
      (node (ref "U2") (pin "35") (pinfunction "PWM1_35") (pintype "output"))
    )
    (net (code "89") (name "unconnected-(U2-PWM2-Pad36)") (class "Default")
      (node (ref "U2") (pin "36") (pinfunction "PWM2_36") (pintype "output"))
    )
    (net (code "90") (name "unconnected-(U2-PWRKEY_OUT-Pad2)") (class "Default")
      (node (ref "U2") (pin "2") (pinfunction "PWRKEY_OUT_2") (pintype "output"))
    )
    (net (code "91") (name "unconnected-(U2-RI-Pad4)") (class "Default")
      (node (ref "U2") (pin "4") (pinfunction "RI_4") (pintype "output"))
    )
    (net (code "92") (name "unconnected-(U2-RTS-Pad8)") (class "Default")
      (node (ref "U2") (pin "8") (pinfunction "RTS_8") (pintype "input"))
    )
    (net (code "93") (name "unconnected-(U2-SCL-Pad38)") (class "Default")
      (node (ref "U2") (pin "38") (pinfunction "SCL_38") (pintype "output"))
    )
    (net (code "94") (name "unconnected-(U2-SDA-Pad37)") (class "Default")
      (node (ref "U2") (pin "37") (pinfunction "SDA_37") (pintype "bidirectional"))
    )
    (net (code "95") (name "unconnected-(U2-SIM_PRESENCE-Pad34)") (class "Default")
      (node (ref "U2") (pin "34") (pinfunction "SIM_PRESENCE_34") (pintype "input"))
    )
    (net (code "96") (name "unconnected-(U2-SPK_N-Pad22)") (class "Default")
      (node (ref "U2") (pin "22") (pinfunction "SPK_N_22") (pintype "output"))
    )
    (net (code "97") (name "unconnected-(U2-SPK_P-Pad21)") (class "Default")
      (node (ref "U2") (pin "21") (pinfunction "SPK_P_21") (pintype "output"))
    )
    (net (code "98") (name "unconnected-(U2-VDD_EXT-Pad15)") (class "Default")
      (node (ref "U2") (pin "15") (pinfunction "VDD_EXT_15") (pintype "output"))
    )
    (net (code "99") (name "unconnected-(U3-ADC6-Pad19)") (class "Default")
      (node (ref "U3") (pin "19") (pinfunction "ADC6_19") (pintype "bidirectional"))
    )
    (net (code "100") (name "unconnected-(U3-ADC7-Pad22)") (class "Default")
      (node (ref "U3") (pin "22") (pinfunction "ADC7_22") (pintype "bidirectional"))
    )
    (net (code "101") (name "unconnected-(U3-PB0(ICP)-Pad12)") (class "Default")
      (node (ref "U3") (pin "12") (pinfunction "PB0(ICP)_12") (pintype "bidirectional"))
    )
    (net (code "102") (name "unconnected-(U3-PB1(OC1A)-Pad13)") (class "Default")
      (node (ref "U3") (pin "13") (pinfunction "PB1(OC1A)_13") (pintype "bidirectional"))
    )
    (net (code "103") (name "unconnected-(U3-PC3(ADC3)-Pad26)") (class "Default")
      (node (ref "U3") (pin "26") (pinfunction "PC3(ADC3)_26") (pintype "bidirectional"))
    )
    (net (code "104") (name "unconnected-(U3-PC4(ADC4{slash}SDA)-Pad27)") (class "Default")
      (node (ref "U3") (pin "27") (pinfunction "PC4(ADC4/SDA)_27") (pintype "bidirectional"))
    )
    (net (code "105") (name "unconnected-(U3-PC5(ADC5{slash}SCL)-Pad28)") (class "Default")
      (node (ref "U3") (pin "28") (pinfunction "PC5(ADC5/SCL)_28") (pintype "bidirectional"))
    )
  )
)
